# sensor_v1.net
KiCad netlist of a schematic drawn in EAGLE
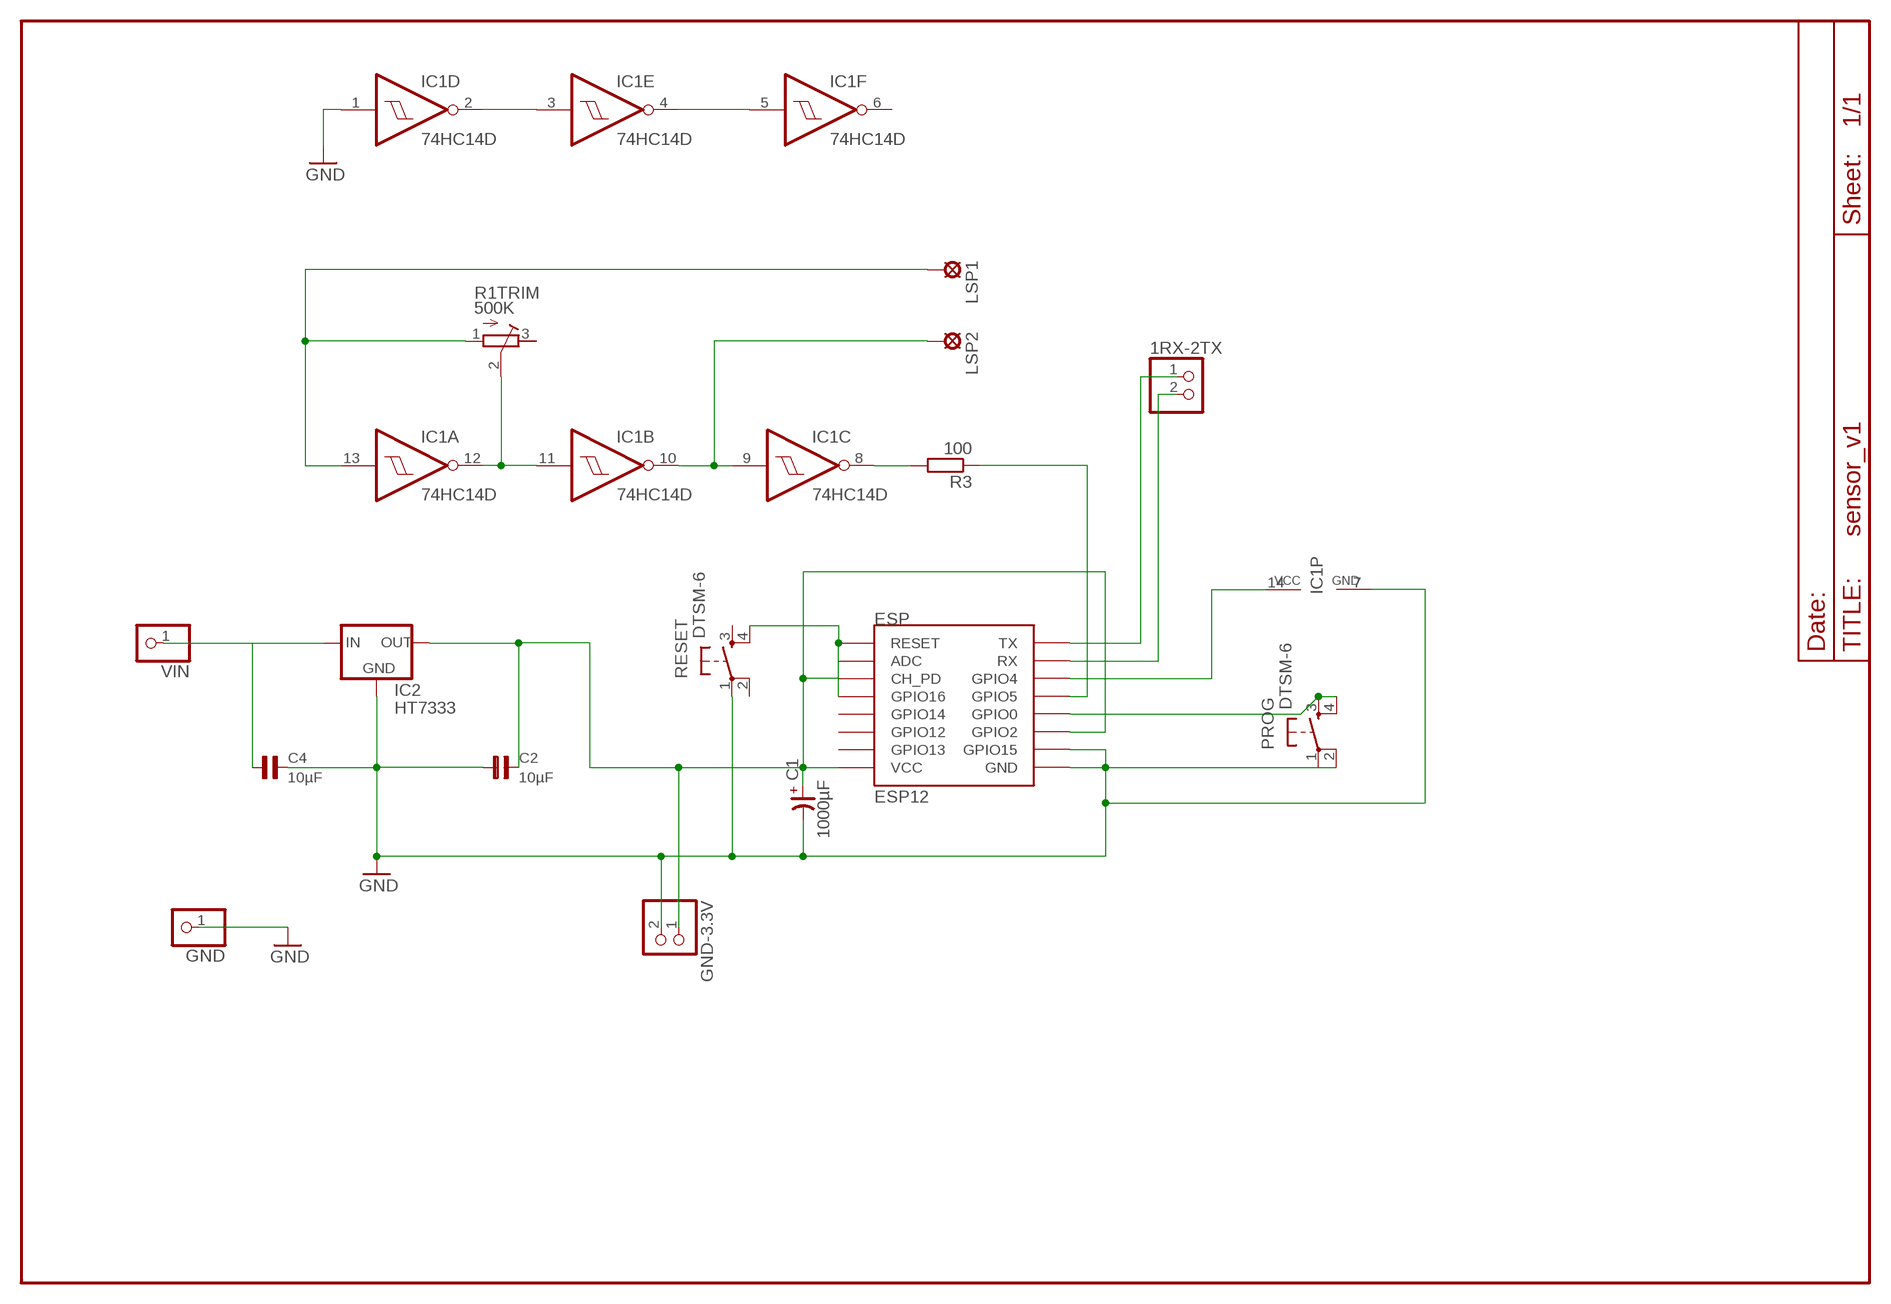
[diagram p0: schematic, sheet 1]

(export (version "E")
  (design (tool "Eeschema 10.0.6"))
  (components
    (comp (ref "1RX-2TX")
      (value "PINHD-1X2")
      (footprint "eagle-import:1X02")
      (libsource (lib "eagle-import") (part "PINHD-1X2"))
    )
    (comp (ref "C1")
      (value "1000µF")
      (footprint "eagle-import:SV-E_F")
      (libsource (lib "eagle-import") (part "CP-SV-E/F"))
    )
    (comp (ref "C2")
      (value "10µF")
      (footprint "eagle-import:1206")
      (libsource (lib "eagle-import") (part "C1206"))
    )
    (comp (ref "C4")
      (value "10µF")
      (footprint "eagle-import:1206")
      (libsource (lib "eagle-import") (part "C1206"))
    )
    (comp (ref "ESP")
      (value "ESP12")
      (footprint "eagle-import:ESP12")
      (libsource (lib "eagle-import") (part "ESP12"))
    )
    (comp (ref "GND")
      (value "PINHD-1X1")
      (footprint "eagle-import:1X01")
      (libsource (lib "eagle-import") (part "PINHD-1X1"))
    )
    (comp (ref "GND-3.3V")
      (value "PINHD-1X2")
      (footprint "eagle-import:1X02")
      (libsource (lib "eagle-import") (part "PINHD-1X2"))
    )
    (comp (ref "IC1")
      (value "74HC14D")
      (footprint "eagle-import:SO14")
      (libsource (lib "eagle-import") (part "7414DHC"))
    )
    (comp (ref "IC2")
      (value "HT7333")
      (footprint "eagle-import:SOT-89")
      (libsource (lib "eagle-import") (part "HT7333"))
    )
    (comp (ref "LSP1")
      (value "LSP11")
      (footprint "eagle-import:LSP11")
      (libsource (lib "eagle-import") (part "LSP11"))
    )
    (comp (ref "LSP2")
      (value "LSP11")
      (footprint "eagle-import:LSP11")
      (libsource (lib "eagle-import") (part "LSP11"))
    )
    (comp (ref "PROG")
      (value "DTSM-6")
      (footprint "eagle-import:DTSM-6")
      (libsource (lib "eagle-import") (part "DTSM-6"))
    )
    (comp (ref "R1TRIM")
      (value "500K")
      (footprint "eagle-import:RTRIM3374")
      (libsource (lib "eagle-import") (part "R-TRIMM3374"))
    )
    (comp (ref "R3")
      (value "100")
      (footprint "eagle-import:R0603")
      (libsource (lib "eagle-import") (part "R-EU_R0603"))
    )
    (comp (ref "RESET")
      (value "DTSM-6")
      (footprint "eagle-import:DTSM-6")
      (libsource (lib "eagle-import") (part "DTSM-6"))
    )
    (comp (ref "VIN")
      (value "PINHD-1X1")
      (footprint "eagle-import:1X01")
      (libsource (lib "eagle-import") (part "PINHD-1X1"))
    )
  )
  (nets
    (net (code "1") (name "/N$9") (class "Default")
      (node (ref "ESP") (pin "GPIO0") (pinfunction "GPIO0_GPIO0") (pintype "bidirectional"))
      (node (ref "IC1") (pin "13") (pinfunction "I_13") (pintype "input"))
      (node (ref "LSP1") (pin "MP") (pinfunction "MP_MP") (pintype "passive"))
      (node (ref "PROG") (pin "3") (pinfunction "3_3") (pintype "passive"))
      (node (ref "PROG") (pin "4") (pinfunction "4_4") (pintype "passive"))
      (node (ref "R1TRIM") (pin "1") (pinfunction "A_1") (pintype "passive"))
    )
    (net (code "2") (name "GND") (class "Default")
      (node (ref "C1") (pin "-") (pinfunction "-_-") (pintype "passive"))
      (node (ref "C2") (pin "1") (pinfunction "1_1") (pintype "passive"))
      (node (ref "C4") (pin "2") (pinfunction "2_2") (pintype "passive"))
      (node (ref "ESP") (pin "GND") (pinfunction "GND_GND") (pintype "bidirectional"))
      (node (ref "ESP") (pin "GPIO15") (pinfunction "GPIO15_GPIO15") (pintype "bidirectional"))
      (node (ref "GND") (pin "1") (pinfunction "1_1") (pintype "passive"))
      (node (ref "GND-3.3V") (pin "2") (pinfunction "2_2") (pintype "passive"))
      (node (ref "IC1") (pin "1") (pinfunction "I_1") (pintype "input"))
      (node (ref "IC1") (pin "7") (pinfunction "GND_7") (pintype "power_in"))
      (node (ref "IC2") (pin "2") (pinfunction "GND_2") (pintype "input"))
      (node (ref "PROG") (pin "1") (pinfunction "1_1") (pintype "passive"))
      (node (ref "PROG") (pin "2") (pinfunction "2_2") (pintype "passive"))
      (node (ref "RESET") (pin "1") (pinfunction "1_1") (pintype "passive"))
    )
    (net (code "3") (name "Net-(1RX-2TX-Pad1)") (class "Default")
      (node (ref "1RX-2TX") (pin "1") (pinfunction "1_1") (pintype "passive"))
      (node (ref "ESP") (pin "TX") (pinfunction "TX_TX") (pintype "bidirectional"))
    )
    (net (code "4") (name "Net-(1RX-2TX-Pad2)") (class "Default")
      (node (ref "1RX-2TX") (pin "2") (pinfunction "2_2") (pintype "passive"))
      (node (ref "ESP") (pin "RX") (pinfunction "RX_RX") (pintype "bidirectional"))
    )
    (net (code "5") (name "Net-(C4-Pad1)") (class "Default")
      (node (ref "C4") (pin "1") (pinfunction "1_1") (pintype "passive"))
      (node (ref "IC2") (pin "3") (pinfunction "IN_3") (pintype "input"))
      (node (ref "IC2") (pin "4") (pinfunction "IN_4") (pintype "input"))
      (node (ref "VIN") (pin "1") (pinfunction "1_1") (pintype "passive"))
    )
    (net (code "6") (name "Net-(ESP-PadGPIO5)") (class "Default")
      (node (ref "ESP") (pin "GPIO5") (pinfunction "GPIO5_GPIO5") (pintype "bidirectional"))
      (node (ref "R3") (pin "1") (pinfunction "1_1") (pintype "passive"))
    )
    (net (code "7") (name "Net-(ESP-PadGPIO16)") (class "Default")
      (node (ref "ESP") (pin "GPIO16") (pinfunction "GPIO16_GPIO16") (pintype "bidirectional"))
      (node (ref "ESP") (pin "RESET") (pinfunction "RESET_RESET") (pintype "bidirectional"))
      (node (ref "RESET") (pin "4") (pinfunction "4_4") (pintype "passive"))
    )
    (net (code "8") (name "Net-(IC1A-O)") (class "Default")
      (node (ref "IC1") (pin "11") (pinfunction "I_11") (pintype "input"))
      (node (ref "IC1") (pin "12") (pinfunction "O_12") (pintype "output"))
      (node (ref "R1TRIM") (pin "2") (pinfunction "S_2") (pintype "passive"))
    )
    (net (code "9") (name "Net-(IC1B-O)") (class "Default")
      (node (ref "IC1") (pin "10") (pinfunction "O_10") (pintype "output"))
      (node (ref "IC1") (pin "9") (pinfunction "I_9") (pintype "input"))
      (node (ref "LSP2") (pin "MP") (pinfunction "MP_MP") (pintype "passive"))
    )
    (net (code "10") (name "Net-(IC1C-O)") (class "Default")
      (node (ref "IC1") (pin "8") (pinfunction "O_8") (pintype "output"))
      (node (ref "R3") (pin "2") (pinfunction "2_2") (pintype "passive"))
    )
    (net (code "11") (name "Net-(IC1D-O)") (class "Default")
      (node (ref "IC1") (pin "2") (pinfunction "O_2") (pintype "output"))
      (node (ref "IC1") (pin "3") (pinfunction "I_3") (pintype "input"))
    )
    (net (code "12") (name "Net-(IC1E-O)") (class "Default")
      (node (ref "IC1") (pin "4") (pinfunction "O_4") (pintype "output"))
      (node (ref "IC1") (pin "5") (pinfunction "I_5") (pintype "input"))
    )
    (net (code "13") (name "Net-(IC1G-VCC)") (class "Default")
      (node (ref "ESP") (pin "GPIO4") (pinfunction "GPIO4_GPIO4") (pintype "bidirectional"))
      (node (ref "IC1") (pin "14") (pinfunction "VCC_14") (pintype "power_in"))
    )
    (net (code "14") (name "Net-(IC2-OUT)") (class "Default")
      (node (ref "C1") (pin "+") (pinfunction "+_+") (pintype "passive"))
      (node (ref "C2") (pin "2") (pinfunction "2_2") (pintype "passive"))
      (node (ref "ESP") (pin "CH_PD") (pinfunction "CH_PD_CH_PD") (pintype "bidirectional"))
      (node (ref "ESP") (pin "GPIO2") (pinfunction "GPIO2_GPIO2") (pintype "bidirectional"))
      (node (ref "ESP") (pin "VCC") (pinfunction "VCC_VCC") (pintype "bidirectional"))
      (node (ref "GND-3.3V") (pin "1") (pinfunction "1_1") (pintype "passive"))
      (node (ref "IC2") (pin "1") (pinfunction "OUT_1") (pintype "passive"))
    )
    (net (code "15") (name "unconnected-(ESP-PadADC)") (class "Default")
      (node (ref "ESP") (pin "ADC") (pinfunction "ADC_ADC") (pintype "bidirectional"))
    )
    (net (code "16") (name "unconnected-(ESP-PadGPIO12)") (class "Default")
      (node (ref "ESP") (pin "GPIO12") (pinfunction "GPIO12_GPIO12") (pintype "bidirectional"))
    )
    (net (code "17") (name "unconnected-(ESP-PadGPIO13)") (class "Default")
      (node (ref "ESP") (pin "GPIO13") (pinfunction "GPIO13_GPIO13") (pintype "bidirectional"))
    )
    (net (code "18") (name "unconnected-(ESP-PadGPIO14)") (class "Default")
      (node (ref "ESP") (pin "GPIO14") (pinfunction "GPIO14_GPIO14") (pintype "bidirectional"))
    )
    (net (code "19") (name "unconnected-(IC1F-O-Pad6)") (class "Default")
      (node (ref "IC1") (pin "6") (pinfunction "O_6") (pintype "output"))
    )
    (net (code "20") (name "unconnected-(R1TRIM-E-Pad3)") (class "Default")
      (node (ref "R1TRIM") (pin "3") (pinfunction "E_3") (pintype "passive"))
    )
    (net (code "21") (name "unconnected-(RESET-Pad2)") (class "Default")
      (node (ref "RESET") (pin "2") (pinfunction "2_2") (pintype "passive"))
    )
    (net (code "22") (name "unconnected-(RESET-Pad3)") (class "Default")
      (node (ref "RESET") (pin "3") (pinfunction "3_3") (pintype "passive"))
    )
  )
)
